# design.net
KiCad netlist of a schematic drawn in Altium Designer
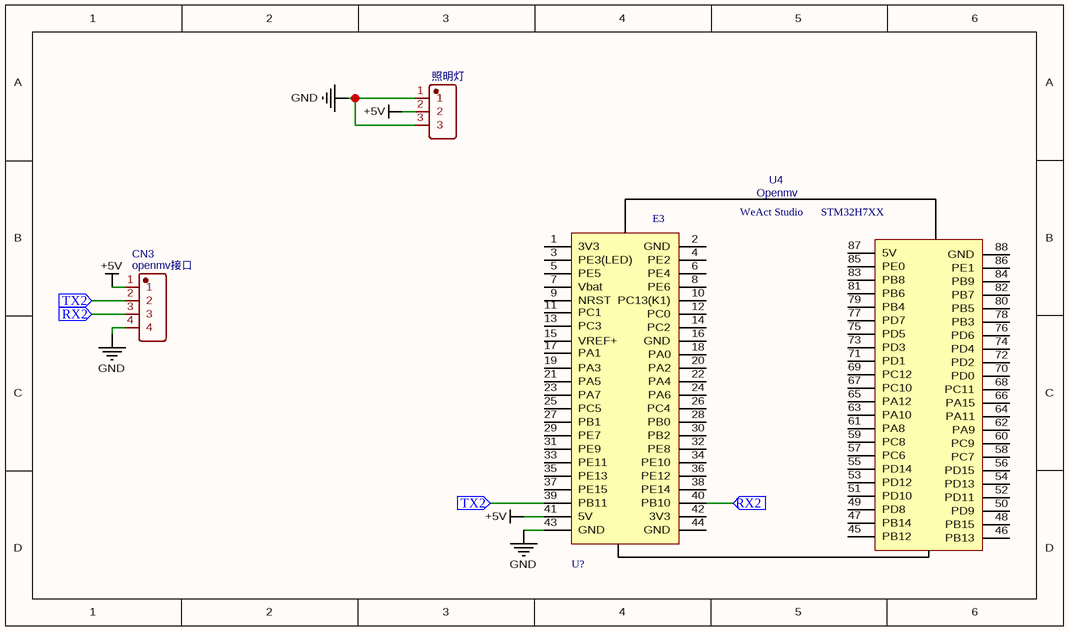
[diagram p0: 原理图_上底板.schdoc]

(export (version "E")
  (design (tool "Eeschema 10.0.6"))
  (components
    (comp (ref "1")
      (value "照明灯")
      (fields
        (field (name "BOM_SUPPLIER PART") "C9900002703")
        (field (name "BOM_MANUFACTURER PART") "PinSocket_1x03_P2.54mm_Vertical")
        (field (name "CONTRIBUTOR") "LCSC")
      )
      (libsource (lib "altium-import") (part "root_0_照明灯_"))
    )
    (comp (ref "CN3")
      (value "openmv接口")
      (fields
        (field (name "BOM_SUPPLIER PART") "C9900002996")
        (field (name "BOM_MANUFACTURER PART") "JTAG")
        (field (name "CONTRIBUTOR") "LCSC")
      )
      (libsource (lib "altium-import") (part "root_0_openmv接口_"))
    )
    (comp (ref "U4")
      (value "Openmv")
      (fields (field (name "CONTRIBUTOR") "Eaglewzw"))
      (libsource (lib "altium-import") (part "root_0_Openmv_"))
    )
  )
  (nets
    (net (code "1") (name "+5V") (class "Default")
      (node (ref "1") (pin "2") (pinfunction "2_2") (pintype "passive"))
      (node (ref "CN3") (pin "1") (pinfunction "1_1") (pintype "passive"))
      (node (ref "U4") (pin "41") (pinfunction "5V_41") (pintype "passive"))
    )
    (net (code "2") (name "/RX2") (class "Default")
      (node (ref "CN3") (pin "3") (pinfunction "3_3") (pintype "passive"))
      (node (ref "U4") (pin "40") (pinfunction "PB10_40") (pintype "passive"))
    )
    (net (code "3") (name "/TX2") (class "Default")
      (node (ref "CN3") (pin "2") (pinfunction "2_2") (pintype "passive"))
      (node (ref "U4") (pin "39") (pinfunction "PB11_39") (pintype "passive"))
    )
    (net (code "4") (name "GND") (class "Default")
      (node (ref "1") (pin "1") (pinfunction "1_1") (pintype "passive"))
      (node (ref "1") (pin "3") (pinfunction "3_3") (pintype "passive"))
      (node (ref "CN3") (pin "4") (pinfunction "4_4") (pintype "passive"))
      (node (ref "U4") (pin "43") (pinfunction "GND_43") (pintype "passive"))
    )
    (net (code "5") (name "unconnected-(U4-3V3-Pad1)") (class "Default")
      (node (ref "U4") (pin "1") (pinfunction "3V3_1") (pintype "passive"))
    )
    (net (code "6") (name "unconnected-(U4-3V3-Pad42)") (class "Default")
      (node (ref "U4") (pin "42") (pinfunction "3V3_42") (pintype "passive"))
    )
    (net (code "7") (name "unconnected-(U4-5V-Pad87)") (class "Default")
      (node (ref "U4") (pin "87") (pinfunction "5V_87") (pintype "passive"))
    )
    (net (code "8") (name "unconnected-(U4-GND-Pad2)") (class "Default")
      (node (ref "U4") (pin "2") (pinfunction "GND_2") (pintype "passive"))
    )
    (net (code "9") (name "unconnected-(U4-GND-Pad16)") (class "Default")
      (node (ref "U4") (pin "16") (pinfunction "GND_16") (pintype "passive"))
    )
    (net (code "10") (name "unconnected-(U4-GND-Pad44)") (class "Default")
      (node (ref "U4") (pin "44") (pinfunction "GND_44") (pintype "passive"))
    )
    (net (code "11") (name "unconnected-(U4-GND-Pad88)") (class "Default")
      (node (ref "U4") (pin "88") (pinfunction "GND_88") (pintype "passive"))
    )
    (net (code "12") (name "unconnected-(U4-NRST-Pad9)") (class "Default")
      (node (ref "U4") (pin "9") (pinfunction "NRST_9") (pintype "passive"))
    )
    (net (code "13") (name "unconnected-(U4-PA0-Pad18)") (class "Default")
      (node (ref "U4") (pin "18") (pinfunction "PA0_18") (pintype "passive"))
    )
    (net (code "14") (name "unconnected-(U4-PA1-Pad17)") (class "Default")
      (node (ref "U4") (pin "17") (pinfunction "PA1_17") (pintype "passive"))
    )
    (net (code "15") (name "unconnected-(U4-PA2-Pad20)") (class "Default")
      (node (ref "U4") (pin "20") (pinfunction "PA2_20") (pintype "passive"))
    )
    (net (code "16") (name "unconnected-(U4-PA3-Pad19)") (class "Default")
      (node (ref "U4") (pin "19") (pinfunction "PA3_19") (pintype "passive"))
    )
    (net (code "17") (name "unconnected-(U4-PA4-Pad22)") (class "Default")
      (node (ref "U4") (pin "22") (pinfunction "PA4_22") (pintype "passive"))
    )
    (net (code "18") (name "unconnected-(U4-PA5-Pad21)") (class "Default")
      (node (ref "U4") (pin "21") (pinfunction "PA5_21") (pintype "passive"))
    )
    (net (code "19") (name "unconnected-(U4-PA6-Pad24)") (class "Default")
      (node (ref "U4") (pin "24") (pinfunction "PA6_24") (pintype "passive"))
    )
    (net (code "20") (name "unconnected-(U4-PA7-Pad23)") (class "Default")
      (node (ref "U4") (pin "23") (pinfunction "PA7_23") (pintype "passive"))
    )
    (net (code "21") (name "unconnected-(U4-PA8-Pad61)") (class "Default")
      (node (ref "U4") (pin "61") (pinfunction "PA8_61") (pintype "passive"))
    )
    (net (code "22") (name "unconnected-(U4-PA9-Pad62)") (class "Default")
      (node (ref "U4") (pin "62") (pinfunction "PA9_62") (pintype "passive"))
    )
    (net (code "23") (name "unconnected-(U4-PA10-Pad63)") (class "Default")
      (node (ref "U4") (pin "63") (pinfunction "PA10_63") (pintype "passive"))
    )
    (net (code "24") (name "unconnected-(U4-PA11-Pad64)") (class "Default")
      (node (ref "U4") (pin "64") (pinfunction "PA11_64") (pintype "passive"))
    )
    (net (code "25") (name "unconnected-(U4-PA12-Pad65)") (class "Default")
      (node (ref "U4") (pin "65") (pinfunction "PA12_65") (pintype "passive"))
    )
    (net (code "26") (name "unconnected-(U4-PA15-Pad66)") (class "Default")
      (node (ref "U4") (pin "66") (pinfunction "PA15_66") (pintype "passive"))
    )
    (net (code "27") (name "unconnected-(U4-PB0-Pad28)") (class "Default")
      (node (ref "U4") (pin "28") (pinfunction "PB0_28") (pintype "passive"))
    )
    (net (code "28") (name "unconnected-(U4-PB1-Pad27)") (class "Default")
      (node (ref "U4") (pin "27") (pinfunction "PB1_27") (pintype "passive"))
    )
    (net (code "29") (name "unconnected-(U4-PB2-Pad30)") (class "Default")
      (node (ref "U4") (pin "30") (pinfunction "PB2_30") (pintype "passive"))
    )
    (net (code "30") (name "unconnected-(U4-PB3-Pad78)") (class "Default")
      (node (ref "U4") (pin "78") (pinfunction "PB3_78") (pintype "passive"))
    )
    (net (code "31") (name "unconnected-(U4-PB4-Pad79)") (class "Default")
      (node (ref "U4") (pin "79") (pinfunction "PB4_79") (pintype "passive"))
    )
    (net (code "32") (name "unconnected-(U4-PB5-Pad80)") (class "Default")
      (node (ref "U4") (pin "80") (pinfunction "PB5_80") (pintype "passive"))
    )
    (net (code "33") (name "unconnected-(U4-PB6-Pad81)") (class "Default")
      (node (ref "U4") (pin "81") (pinfunction "PB6_81") (pintype "passive"))
    )
    (net (code "34") (name "unconnected-(U4-PB7-Pad82)") (class "Default")
      (node (ref "U4") (pin "82") (pinfunction "PB7_82") (pintype "passive"))
    )
    (net (code "35") (name "unconnected-(U4-PB8-Pad83)") (class "Default")
      (node (ref "U4") (pin "83") (pinfunction "PB8_83") (pintype "passive"))
    )
    (net (code "36") (name "unconnected-(U4-PB9-Pad84)") (class "Default")
      (node (ref "U4") (pin "84") (pinfunction "PB9_84") (pintype "passive"))
    )
    (net (code "37") (name "unconnected-(U4-PB12-Pad45)") (class "Default")
      (node (ref "U4") (pin "45") (pinfunction "PB12_45") (pintype "passive"))
    )
    (net (code "38") (name "unconnected-(U4-PB13-Pad46)") (class "Default")
      (node (ref "U4") (pin "46") (pinfunction "PB13_46") (pintype "passive"))
    )
    (net (code "39") (name "unconnected-(U4-PB14-Pad47)") (class "Default")
      (node (ref "U4") (pin "47") (pinfunction "PB14_47") (pintype "passive"))
    )
    (net (code "40") (name "unconnected-(U4-PB15-Pad48)") (class "Default")
      (node (ref "U4") (pin "48") (pinfunction "PB15_48") (pintype "passive"))
    )
    (net (code "41") (name "unconnected-(U4-PC0-Pad12)") (class "Default")
      (node (ref "U4") (pin "12") (pinfunction "PC0_12") (pintype "passive"))
    )
    (net (code "42") (name "unconnected-(U4-PC1-Pad11)") (class "Default")
      (node (ref "U4") (pin "11") (pinfunction "PC1_11") (pintype "passive"))
    )
    (net (code "43") (name "unconnected-(U4-PC2-Pad14)") (class "Default")
      (node (ref "U4") (pin "14") (pinfunction "PC2_14") (pintype "passive"))
    )
    (net (code "44") (name "unconnected-(U4-PC3-Pad13)") (class "Default")
      (node (ref "U4") (pin "13") (pinfunction "PC3_13") (pintype "passive"))
    )
    (net (code "45") (name "unconnected-(U4-PC4-Pad26)") (class "Default")
      (node (ref "U4") (pin "26") (pinfunction "PC4_26") (pintype "passive"))
    )
    (net (code "46") (name "unconnected-(U4-PC5-Pad25)") (class "Default")
      (node (ref "U4") (pin "25") (pinfunction "PC5_25") (pintype "passive"))
    )
    (net (code "47") (name "unconnected-(U4-PC6-Pad57)") (class "Default")
      (node (ref "U4") (pin "57") (pinfunction "PC6_57") (pintype "passive"))
    )
    (net (code "48") (name "unconnected-(U4-PC7-Pad58)") (class "Default")
      (node (ref "U4") (pin "58") (pinfunction "PC7_58") (pintype "passive"))
    )
    (net (code "49") (name "unconnected-(U4-PC8-Pad59)") (class "Default")
      (node (ref "U4") (pin "59") (pinfunction "PC8_59") (pintype "passive"))
    )
    (net (code "50") (name "unconnected-(U4-PC9-Pad60)") (class "Default")
      (node (ref "U4") (pin "60") (pinfunction "PC9_60") (pintype "passive"))
    )
    (net (code "51") (name "unconnected-(U4-PC10-Pad67)") (class "Default")
      (node (ref "U4") (pin "67") (pinfunction "PC10_67") (pintype "passive"))
    )
    (net (code "52") (name "unconnected-(U4-PC11-Pad68)") (class "Default")
      (node (ref "U4") (pin "68") (pinfunction "PC11_68") (pintype "passive"))
    )
    (net (code "53") (name "unconnected-(U4-PC12-Pad69)") (class "Default")
      (node (ref "U4") (pin "69") (pinfunction "PC12_69") (pintype "passive"))
    )
    (net (code "54") (name "unconnected-(U4-PC13(K1)-Pad10)") (class "Default")
      (node (ref "U4") (pin "10") (pinfunction "PC13(K1)_10") (pintype "passive"))
    )
    (net (code "55") (name "unconnected-(U4-PD0-Pad70)") (class "Default")
      (node (ref "U4") (pin "70") (pinfunction "PD0_70") (pintype "passive"))
    )
    (net (code "56") (name "unconnected-(U4-PD1-Pad71)") (class "Default")
      (node (ref "U4") (pin "71") (pinfunction "PD1_71") (pintype "passive"))
    )
    (net (code "57") (name "unconnected-(U4-PD2-Pad72)") (class "Default")
      (node (ref "U4") (pin "72") (pinfunction "PD2_72") (pintype "passive"))
    )
    (net (code "58") (name "unconnected-(U4-PD3-Pad73)") (class "Default")
      (node (ref "U4") (pin "73") (pinfunction "PD3_73") (pintype "passive"))
    )
    (net (code "59") (name "unconnected-(U4-PD4-Pad74)") (class "Default")
      (node (ref "U4") (pin "74") (pinfunction "PD4_74") (pintype "passive"))
    )
    (net (code "60") (name "unconnected-(U4-PD5-Pad75)") (class "Default")
      (node (ref "U4") (pin "75") (pinfunction "PD5_75") (pintype "passive"))
    )
    (net (code "61") (name "unconnected-(U4-PD6-Pad76)") (class "Default")
      (node (ref "U4") (pin "76") (pinfunction "PD6_76") (pintype "passive"))
    )
    (net (code "62") (name "unconnected-(U4-PD7-Pad77)") (class "Default")
      (node (ref "U4") (pin "77") (pinfunction "PD7_77") (pintype "passive"))
    )
    (net (code "63") (name "unconnected-(U4-PD8-Pad49)") (class "Default")
      (node (ref "U4") (pin "49") (pinfunction "PD8_49") (pintype "passive"))
    )
    (net (code "64") (name "unconnected-(U4-PD9-Pad50)") (class "Default")
      (node (ref "U4") (pin "50") (pinfunction "PD9_50") (pintype "passive"))
    )
    (net (code "65") (name "unconnected-(U4-PD10-Pad51)") (class "Default")
      (node (ref "U4") (pin "51") (pinfunction "PD10_51") (pintype "passive"))
    )
    (net (code "66") (name "unconnected-(U4-PD11-Pad52)") (class "Default")
      (node (ref "U4") (pin "52") (pinfunction "PD11_52") (pintype "passive"))
    )
    (net (code "67") (name "unconnected-(U4-PD12-Pad53)") (class "Default")
      (node (ref "U4") (pin "53") (pinfunction "PD12_53") (pintype "passive"))
    )
    (net (code "68") (name "unconnected-(U4-PD13-Pad54)") (class "Default")
      (node (ref "U4") (pin "54") (pinfunction "PD13_54") (pintype "passive"))
    )
    (net (code "69") (name "unconnected-(U4-PD14-Pad55)") (class "Default")
      (node (ref "U4") (pin "55") (pinfunction "PD14_55") (pintype "passive"))
    )
    (net (code "70") (name "unconnected-(U4-PD15-Pad56)") (class "Default")
      (node (ref "U4") (pin "56") (pinfunction "PD15_56") (pintype "passive"))
    )
    (net (code "71") (name "unconnected-(U4-PE0-Pad85)") (class "Default")
      (node (ref "U4") (pin "85") (pinfunction "PE0_85") (pintype "passive"))
    )
    (net (code "72") (name "unconnected-(U4-PE1-Pad86)") (class "Default")
      (node (ref "U4") (pin "86") (pinfunction "PE1_86") (pintype "passive"))
    )
    (net (code "73") (name "unconnected-(U4-PE2-Pad4)") (class "Default")
      (node (ref "U4") (pin "4") (pinfunction "PE2_4") (pintype "passive"))
    )
    (net (code "74") (name "unconnected-(U4-PE3(LED)-Pad3)") (class "Default")
      (node (ref "U4") (pin "3") (pinfunction "PE3(LED)_3") (pintype "passive"))
    )
    (net (code "75") (name "unconnected-(U4-PE4-Pad6)") (class "Default")
      (node (ref "U4") (pin "6") (pinfunction "PE4_6") (pintype "passive"))
    )
    (net (code "76") (name "unconnected-(U4-PE5-Pad5)") (class "Default")
      (node (ref "U4") (pin "5") (pinfunction "PE5_5") (pintype "passive"))
    )
    (net (code "77") (name "unconnected-(U4-PE6-Pad8)") (class "Default")
      (node (ref "U4") (pin "8") (pinfunction "PE6_8") (pintype "passive"))
    )
    (net (code "78") (name "unconnected-(U4-PE7-Pad29)") (class "Default")
      (node (ref "U4") (pin "29") (pinfunction "PE7_29") (pintype "passive"))
    )
    (net (code "79") (name "unconnected-(U4-PE8-Pad32)") (class "Default")
      (node (ref "U4") (pin "32") (pinfunction "PE8_32") (pintype "passive"))
    )
    (net (code "80") (name "unconnected-(U4-PE9-Pad31)") (class "Default")
      (node (ref "U4") (pin "31") (pinfunction "PE9_31") (pintype "passive"))
    )
    (net (code "81") (name "unconnected-(U4-PE10-Pad34)") (class "Default")
      (node (ref "U4") (pin "34") (pinfunction "PE10_34") (pintype "passive"))
    )
    (net (code "82") (name "unconnected-(U4-PE11-Pad33)") (class "Default")
      (node (ref "U4") (pin "33") (pinfunction "PE11_33") (pintype "passive"))
    )
    (net (code "83") (name "unconnected-(U4-PE12-Pad36)") (class "Default")
      (node (ref "U4") (pin "36") (pinfunction "PE12_36") (pintype "passive"))
    )
    (net (code "84") (name "unconnected-(U4-PE13-Pad35)") (class "Default")
      (node (ref "U4") (pin "35") (pinfunction "PE13_35") (pintype "passive"))
    )
    (net (code "85") (name "unconnected-(U4-PE14-Pad38)") (class "Default")
      (node (ref "U4") (pin "38") (pinfunction "PE14_38") (pintype "passive"))
    )
    (net (code "86") (name "unconnected-(U4-PE15-Pad37)") (class "Default")
      (node (ref "U4") (pin "37") (pinfunction "PE15_37") (pintype "passive"))
    )
    (net (code "87") (name "unconnected-(U4-VREF+-Pad15)") (class "Default")
      (node (ref "U4") (pin "15") (pinfunction "VREF+_15") (pintype "passive"))
    )
    (net (code "88") (name "unconnected-(U4-Vbat-Pad7)") (class "Default")
      (node (ref "U4") (pin "7") (pinfunction "Vbat_7") (pintype "passive"))
    )
  )
)
